# BaseMachine_Exio_Board.net
KiCad netlist of a schematic drawn in EAGLE
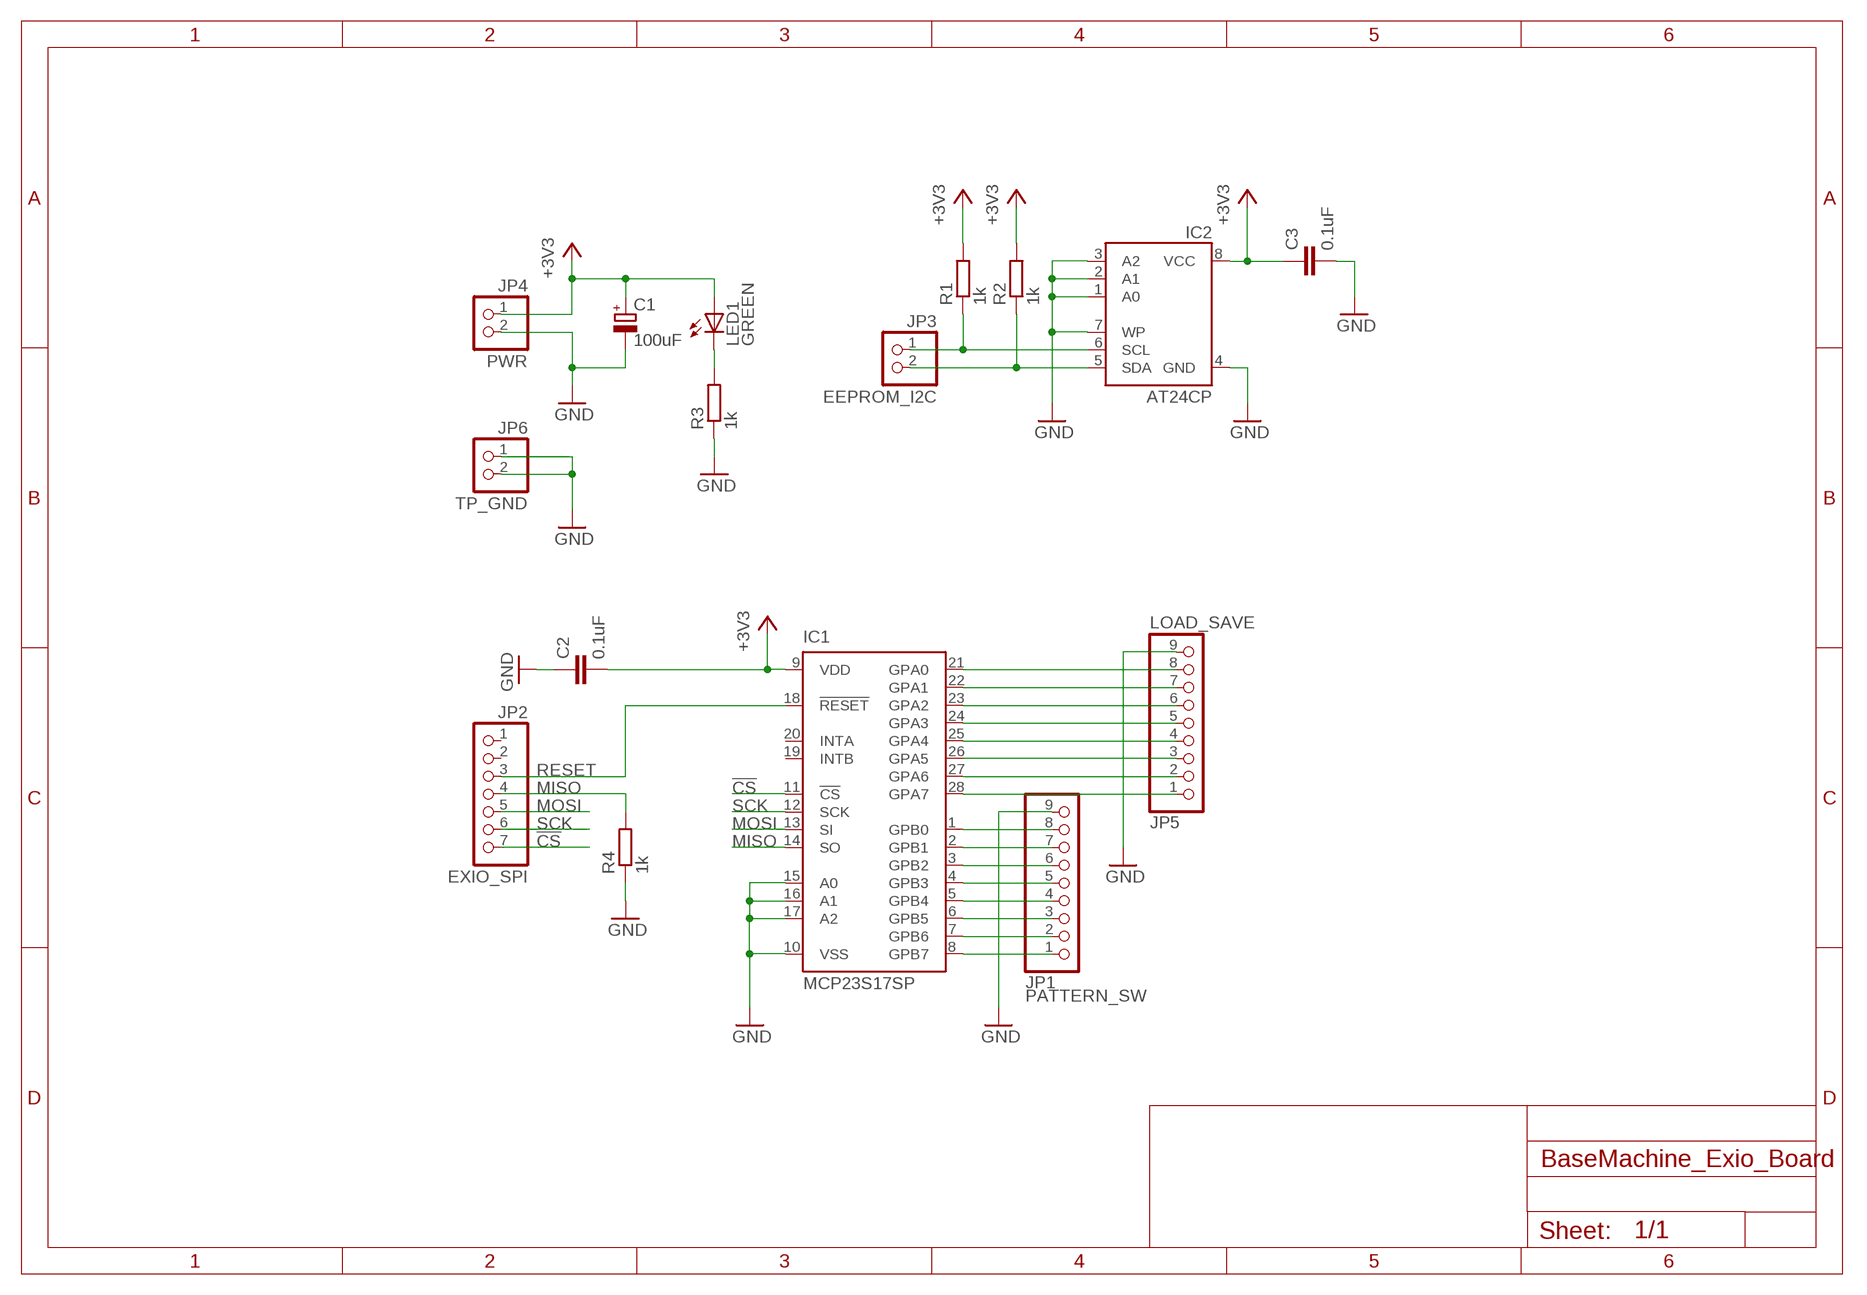
[diagram p0: schematic, sheet 1]

(export (version "E")
  (design (tool "Eeschema 10.0.6"))
  (components
    (comp (ref "C1")
      (value "100uF")
      (footprint "eagle-import:SANYO-OSCON_C6")
      (libsource (lib "eagle-import") (part "CPOL-EUSANYO_C6"))
    )
    (comp (ref "C2")
      (value "0.1uF")
      (footprint "eagle-import:C025-024X044")
      (libsource (lib "eagle-import") (part "C-EU025-024X044"))
    )
    (comp (ref "C3")
      (value "0.1uF")
      (footprint "eagle-import:C025-024X044")
      (libsource (lib "eagle-import") (part "C-EU025-024X044"))
    )
    (comp (ref "IC1")
      (value "MCP23S17SP")
      (footprint "eagle-import:DIL28-3")
      (fields (field (name "MF") "MICROCHIP") (field (name "MPN") "MCP23S17-E/SP"))
      (libsource (lib "eagle-import") (part "MCP23S17SP"))
    )
    (comp (ref "IC2")
      (value "AT24CP")
      (footprint "eagle-import:DIL08")
      (fields (field (name "MPN") "AT24C1024BW-SH-B"))
      (libsource (lib "eagle-import") (part "AT24CP"))
    )
    (comp (ref "JP1")
      (value "PATTERN_SW")
      (footprint "eagle-import:1X09_90")
      (libsource (lib "eagle-import") (part "PINHD-1X9/90"))
    )
    (comp (ref "JP2")
      (value "EXIO_SPI")
      (footprint "eagle-import:1X07_90")
      (libsource (lib "eagle-import") (part "PINHD-1X7/90"))
    )
    (comp (ref "JP3")
      (value "EEPROM_I2C")
      (footprint "eagle-import:1X02_90")
      (libsource (lib "eagle-import") (part "PINHD-1X2/90"))
    )
    (comp (ref "JP4")
      (value "PWR")
      (footprint "eagle-import:1X02_90")
      (libsource (lib "eagle-import") (part "PINHD-1X2/90"))
    )
    (comp (ref "JP5")
      (value "LOAD_SAVE")
      (footprint "eagle-import:1X09_90")
      (libsource (lib "eagle-import") (part "PINHD-1X9/90"))
    )
    (comp (ref "JP6")
      (value "TP_GND")
      (footprint "eagle-import:1X02")
      (libsource (lib "eagle-import") (part "PINHD-1X2"))
    )
    (comp (ref "LED1")
      (value "GREEN")
      (footprint "eagle-import:LED3MM")
      (libsource (lib "eagle-import") (part "LED3MM"))
    )
    (comp (ref "R1")
      (value "1k")
      (footprint "eagle-import:0207_7")
      (libsource (lib "eagle-import") (part "R-EU_0207/7"))
    )
    (comp (ref "R2")
      (value "1k")
      (footprint "eagle-import:0207_7")
      (libsource (lib "eagle-import") (part "R-EU_0207/7"))
    )
    (comp (ref "R3")
      (value "1k")
      (footprint "eagle-import:0207_7")
      (libsource (lib "eagle-import") (part "R-EU_0207/7"))
    )
    (comp (ref "R4")
      (value "1k")
      (footprint "eagle-import:0207_7")
      (libsource (lib "eagle-import") (part "R-EU_0207/7"))
    )
  )
  (nets
    (net (code "1") (name "+3V3") (class "Default")
      (node (ref "C1") (pin "+") (pinfunction "+_+") (pintype "passive"))
      (node (ref "C2") (pin "2") (pinfunction "2_2") (pintype "passive"))
      (node (ref "C3") (pin "1") (pinfunction "1_1") (pintype "passive"))
      (node (ref "IC1") (pin "9") (pinfunction "VDD_9") (pintype "power_in"))
      (node (ref "IC2") (pin "8") (pinfunction "VCC_8") (pintype "power_in"))
      (node (ref "JP4") (pin "1") (pinfunction "1_1") (pintype "passive"))
      (node (ref "LED1") (pin "A") (pinfunction "A_A") (pintype "passive"))
      (node (ref "R1") (pin "2") (pinfunction "2_2") (pintype "passive"))
      (node (ref "R2") (pin "2") (pinfunction "2_2") (pintype "passive"))
    )
    (net (code "2") (name "/MISO") (class "Default")
      (node (ref "IC1") (pin "14") (pinfunction "SO_14") (pintype "output"))
      (node (ref "JP2") (pin "4") (pinfunction "4_4") (pintype "passive"))
      (node (ref "R4") (pin "2") (pinfunction "2_2") (pintype "passive"))
    )
    (net (code "3") (name "/MOSI") (class "Default")
      (node (ref "IC1") (pin "13") (pinfunction "SI_13") (pintype "input"))
      (node (ref "JP2") (pin "5") (pinfunction "5_5") (pintype "passive"))
    )
    (net (code "4") (name "/RESET") (class "Default")
      (node (ref "IC1") (pin "18") (pinfunction "~{RESET}_18") (pintype "input"))
      (node (ref "JP2") (pin "3") (pinfunction "3_3") (pintype "passive"))
    )
    (net (code "5") (name "/SCK") (class "Default")
      (node (ref "IC1") (pin "12") (pinfunction "SCK_12") (pintype "input"))
      (node (ref "JP2") (pin "6") (pinfunction "6_6") (pintype "passive"))
    )
    (net (code "6") (name "/~{CS}") (class "Default")
      (node (ref "IC1") (pin "11") (pinfunction "~{CS}_11") (pintype "input"))
      (node (ref "JP2") (pin "7") (pinfunction "7_7") (pintype "passive"))
    )
    (net (code "7") (name "GND") (class "Default")
      (node (ref "C1") (pin "-") (pinfunction "-_-") (pintype "passive"))
      (node (ref "C2") (pin "1") (pinfunction "1_1") (pintype "passive"))
      (node (ref "C3") (pin "2") (pinfunction "2_2") (pintype "passive"))
      (node (ref "IC1") (pin "10") (pinfunction "VSS_10") (pintype "power_in"))
      (node (ref "IC1") (pin "15") (pinfunction "A0_15") (pintype "input"))
      (node (ref "IC1") (pin "16") (pinfunction "A1_16") (pintype "input"))
      (node (ref "IC1") (pin "17") (pinfunction "A2_17") (pintype "input"))
      (node (ref "IC2") (pin "1") (pinfunction "A0_1") (pintype "input"))
      (node (ref "IC2") (pin "2") (pinfunction "A1_2") (pintype "input"))
      (node (ref "IC2") (pin "3") (pinfunction "A2_3") (pintype "input"))
      (node (ref "IC2") (pin "4") (pinfunction "GND_4") (pintype "power_in"))
      (node (ref "IC2") (pin "7") (pinfunction "WP_7") (pintype "input"))
      (node (ref "JP1") (pin "9") (pinfunction "9_9") (pintype "passive"))
      (node (ref "JP4") (pin "2") (pinfunction "2_2") (pintype "passive"))
      (node (ref "JP5") (pin "9") (pinfunction "9_9") (pintype "passive"))
      (node (ref "JP6") (pin "1") (pinfunction "1_1") (pintype "passive"))
      (node (ref "JP6") (pin "2") (pinfunction "2_2") (pintype "passive"))
      (node (ref "R3") (pin "1") (pinfunction "1_1") (pintype "passive"))
      (node (ref "R4") (pin "1") (pinfunction "1_1") (pintype "passive"))
    )
    (net (code "8") (name "Net-(IC1-GPA0)") (class "Default")
      (node (ref "IC1") (pin "21") (pinfunction "GPA0_21") (pintype "bidirectional"))
      (node (ref "JP5") (pin "8") (pinfunction "8_8") (pintype "passive"))
    )
    (net (code "9") (name "Net-(IC1-GPA1)") (class "Default")
      (node (ref "IC1") (pin "22") (pinfunction "GPA1_22") (pintype "bidirectional"))
      (node (ref "JP5") (pin "7") (pinfunction "7_7") (pintype "passive"))
    )
    (net (code "10") (name "Net-(IC1-GPA2)") (class "Default")
      (node (ref "IC1") (pin "23") (pinfunction "GPA2_23") (pintype "bidirectional"))
      (node (ref "JP5") (pin "6") (pinfunction "6_6") (pintype "passive"))
    )
    (net (code "11") (name "Net-(IC1-GPA3)") (class "Default")
      (node (ref "IC1") (pin "24") (pinfunction "GPA3_24") (pintype "bidirectional"))
      (node (ref "JP5") (pin "5") (pinfunction "5_5") (pintype "passive"))
    )
    (net (code "12") (name "Net-(IC1-GPA4)") (class "Default")
      (node (ref "IC1") (pin "25") (pinfunction "GPA4_25") (pintype "bidirectional"))
      (node (ref "JP5") (pin "4") (pinfunction "4_4") (pintype "passive"))
    )
    (net (code "13") (name "Net-(IC1-GPA5)") (class "Default")
      (node (ref "IC1") (pin "26") (pinfunction "GPA5_26") (pintype "bidirectional"))
      (node (ref "JP5") (pin "3") (pinfunction "3_3") (pintype "passive"))
    )
    (net (code "14") (name "Net-(IC1-GPA6)") (class "Default")
      (node (ref "IC1") (pin "27") (pinfunction "GPA6_27") (pintype "bidirectional"))
      (node (ref "JP5") (pin "2") (pinfunction "2_2") (pintype "passive"))
    )
    (net (code "15") (name "Net-(IC1-GPA7)") (class "Default")
      (node (ref "IC1") (pin "28") (pinfunction "GPA7_28") (pintype "bidirectional"))
      (node (ref "JP5") (pin "1") (pinfunction "1_1") (pintype "passive"))
    )
    (net (code "16") (name "Net-(IC1-GPB0)") (class "Default")
      (node (ref "IC1") (pin "1") (pinfunction "GPB0_1") (pintype "bidirectional"))
      (node (ref "JP1") (pin "8") (pinfunction "8_8") (pintype "passive"))
    )
    (net (code "17") (name "Net-(IC1-GPB1)") (class "Default")
      (node (ref "IC1") (pin "2") (pinfunction "GPB1_2") (pintype "bidirectional"))
      (node (ref "JP1") (pin "7") (pinfunction "7_7") (pintype "passive"))
    )
    (net (code "18") (name "Net-(IC1-GPB2)") (class "Default")
      (node (ref "IC1") (pin "3") (pinfunction "GPB2_3") (pintype "bidirectional"))
      (node (ref "JP1") (pin "6") (pinfunction "6_6") (pintype "passive"))
    )
    (net (code "19") (name "Net-(IC1-GPB3)") (class "Default")
      (node (ref "IC1") (pin "4") (pinfunction "GPB3_4") (pintype "bidirectional"))
      (node (ref "JP1") (pin "5") (pinfunction "5_5") (pintype "passive"))
    )
    (net (code "20") (name "Net-(IC1-GPB4)") (class "Default")
      (node (ref "IC1") (pin "5") (pinfunction "GPB4_5") (pintype "bidirectional"))
      (node (ref "JP1") (pin "4") (pinfunction "4_4") (pintype "passive"))
    )
    (net (code "21") (name "Net-(IC1-GPB5)") (class "Default")
      (node (ref "IC1") (pin "6") (pinfunction "GPB5_6") (pintype "bidirectional"))
      (node (ref "JP1") (pin "3") (pinfunction "3_3") (pintype "passive"))
    )
    (net (code "22") (name "Net-(IC1-GPB6)") (class "Default")
      (node (ref "IC1") (pin "7") (pinfunction "GPB6_7") (pintype "bidirectional"))
      (node (ref "JP1") (pin "2") (pinfunction "2_2") (pintype "passive"))
    )
    (net (code "23") (name "Net-(IC1-GPB7)") (class "Default")
      (node (ref "IC1") (pin "8") (pinfunction "GPB7_8") (pintype "bidirectional"))
      (node (ref "JP1") (pin "1") (pinfunction "1_1") (pintype "passive"))
    )
    (net (code "24") (name "Net-(IC2-SCL)") (class "Default")
      (node (ref "IC2") (pin "6") (pinfunction "SCL_6") (pintype "bidirectional"))
      (node (ref "JP3") (pin "1") (pinfunction "1_1") (pintype "passive"))
      (node (ref "R1") (pin "1") (pinfunction "1_1") (pintype "passive"))
    )
    (net (code "25") (name "Net-(IC2-SDA)") (class "Default")
      (node (ref "IC2") (pin "5") (pinfunction "SDA_5") (pintype "bidirectional"))
      (node (ref "JP3") (pin "2") (pinfunction "2_2") (pintype "passive"))
      (node (ref "R2") (pin "1") (pinfunction "1_1") (pintype "passive"))
    )
    (net (code "26") (name "Net-(LED1-C)") (class "Default")
      (node (ref "LED1") (pin "K") (pinfunction "C_K") (pintype "passive"))
      (node (ref "R3") (pin "2") (pinfunction "2_2") (pintype "passive"))
    )
    (net (code "27") (name "unconnected-(IC1-INTA-Pad20)") (class "Default")
      (node (ref "IC1") (pin "20") (pinfunction "INTA_20") (pintype "output"))
    )
    (net (code "28") (name "unconnected-(IC1-INTB-Pad19)") (class "Default")
      (node (ref "IC1") (pin "19") (pinfunction "INTB_19") (pintype "output"))
    )
    (net (code "29") (name "unconnected-(JP2-Pad1)") (class "Default")
      (node (ref "JP2") (pin "1") (pinfunction "1_1") (pintype "passive"))
    )
    (net (code "30") (name "unconnected-(JP2-Pad2)") (class "Default")
      (node (ref "JP2") (pin "2") (pinfunction "2_2") (pintype "passive"))
    )
  )
)
